# untitled.net
KiCad netlist of a schematic drawn in EAGLE
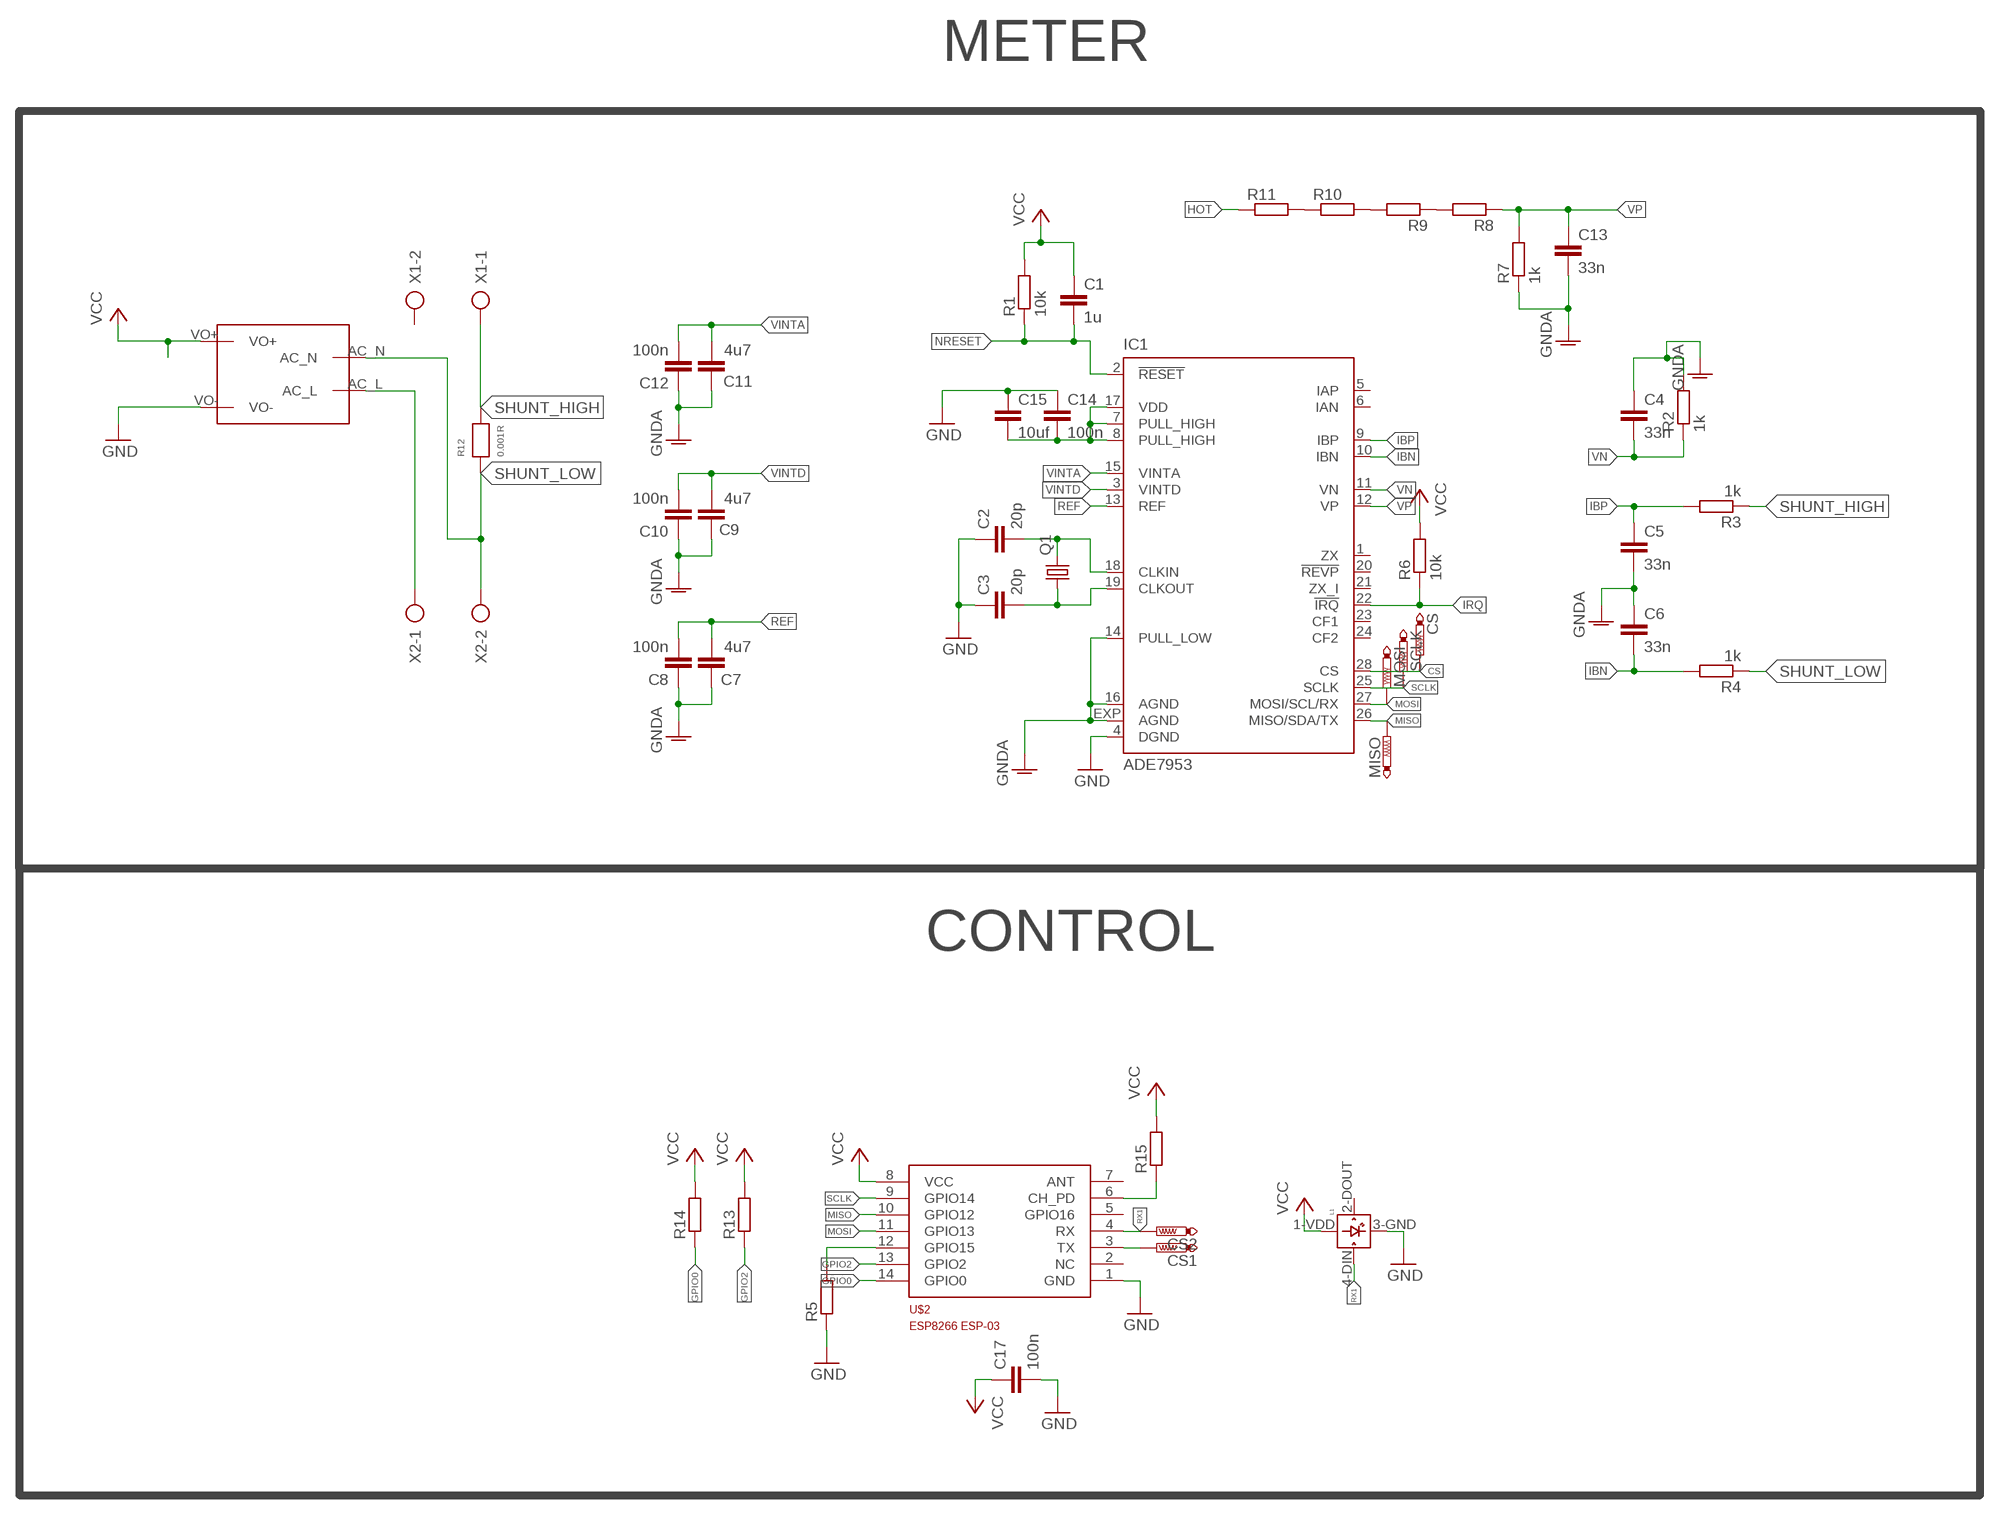
[diagram p0: schematic, sheet 1]

(export (version "E")
  (design (tool "Eeschema 10.0.6"))
  (components
    (comp (ref "C1")
      (value "1u")
      (footprint "eagle-import:C0805")
      (libsource (lib "eagle-import") (part "C-EUC0805"))
    )
    (comp (ref "C2")
      (value "20p")
      (footprint "eagle-import:C0805")
      (libsource (lib "eagle-import") (part "C-EUC0805"))
    )
    (comp (ref "C3")
      (value "20p")
      (footprint "eagle-import:C0805")
      (libsource (lib "eagle-import") (part "C-EUC0805"))
    )
    (comp (ref "C4")
      (value "33n")
      (footprint "eagle-import:C0805")
      (libsource (lib "eagle-import") (part "C-EUC0805"))
    )
    (comp (ref "C5")
      (value "33n")
      (footprint "eagle-import:C0805")
      (libsource (lib "eagle-import") (part "C-EUC0805"))
    )
    (comp (ref "C6")
      (value "33n")
      (footprint "eagle-import:C0805")
      (libsource (lib "eagle-import") (part "C-EUC0805"))
    )
    (comp (ref "C7")
      (value "4u7")
      (footprint "eagle-import:C0805")
      (libsource (lib "eagle-import") (part "C-EUC0805"))
    )
    (comp (ref "C8")
      (value "100n")
      (footprint "eagle-import:C0805")
      (libsource (lib "eagle-import") (part "C-EUC0805"))
    )
    (comp (ref "C9")
      (value "4u7")
      (footprint "eagle-import:C0805")
      (libsource (lib "eagle-import") (part "C-EUC0805"))
    )
    (comp (ref "C10")
      (value "100n")
      (footprint "eagle-import:C0805")
      (libsource (lib "eagle-import") (part "C-EUC0805"))
    )
    (comp (ref "C11")
      (value "4u7")
      (footprint "eagle-import:C0805")
      (libsource (lib "eagle-import") (part "C-EUC0805"))
    )
    (comp (ref "C12")
      (value "100n")
      (footprint "eagle-import:C0805")
      (libsource (lib "eagle-import") (part "C-EUC0805"))
    )
    (comp (ref "C13")
      (value "33n")
      (footprint "eagle-import:C0805")
      (libsource (lib "eagle-import") (part "C-EUC0805"))
    )
    (comp (ref "C14")
      (value "100n")
      (footprint "eagle-import:C0805")
      (libsource (lib "eagle-import") (part "C-EUC0805"))
    )
    (comp (ref "C15")
      (value "10uf")
      (footprint "eagle-import:C0805")
      (libsource (lib "eagle-import") (part "C-EUC0805"))
    )
    (comp (ref "C17")
      (value "100n")
      (footprint "eagle-import:C0805")
      (libsource (lib "eagle-import") (part "C-EUC0805"))
    )
    (comp (ref "CS")
      (value "PTR1B1,27")
      (footprint "eagle-import:B1,27")
      (libsource (lib "eagle-import") (part "PTR1B1,27"))
    )
    (comp (ref "CS1")
      (value "PTR1B1,27")
      (footprint "eagle-import:B1,27")
      (libsource (lib "eagle-import") (part "PTR1B1,27"))
    )
    (comp (ref "CS2")
      (value "PTR1B1,27")
      (footprint "eagle-import:B1,27")
      (libsource (lib "eagle-import") (part "PTR1B1,27"))
    )
    (comp (ref "IC1")
      (value "ADE7953")
      (footprint "eagle-import:QFN28-ML")
      (libsource (lib "eagle-import") (part "ADE7953"))
    )
    (comp (ref "L1")
      (value "WS2812B")
      (footprint "eagle-import:WS2812B")
      (libsource (lib "eagle-import") (part "WS2812B"))
    )
    (comp (ref "MISO")
      (value "PTR1B1,27")
      (footprint "eagle-import:B1,27")
      (libsource (lib "eagle-import") (part "PTR1B1,27"))
    )
    (comp (ref "MOSI")
      (value "PTR1B1,27")
      (footprint "eagle-import:B1,27")
      (libsource (lib "eagle-import") (part "PTR1B1,27"))
    )
    (comp (ref "Q1")
      (value "CRYSTALHC49UP")
      (footprint "eagle-import:HC49UP")
      (libsource (lib "eagle-import") (part "CRYSTALHC49UP"))
    )
    (comp (ref "R1")
      (value "10k")
      (footprint "eagle-import:R0805")
      (libsource (lib "eagle-import") (part "R-EU_R0805"))
    )
    (comp (ref "R2")
      (value "1k")
      (footprint "eagle-import:R0805")
      (libsource (lib "eagle-import") (part "R-EU_R0805"))
    )
    (comp (ref "R3")
      (value "1k")
      (footprint "eagle-import:R0805")
      (libsource (lib "eagle-import") (part "R-EU_R0805"))
    )
    (comp (ref "R4")
      (value "1k")
      (footprint "eagle-import:R0805")
      (libsource (lib "eagle-import") (part "R-EU_R0805"))
    )
    (comp (ref "R5")
      (value "R-EU_R0603")
      (footprint "eagle-import:R0603")
      (libsource (lib "eagle-import") (part "R-EU_R0603"))
    )
    (comp (ref "R6")
      (value "10k")
      (footprint "eagle-import:R0805")
      (libsource (lib "eagle-import") (part "R-EU_R0805"))
    )
    (comp (ref "R7")
      (value "1k")
      (footprint "eagle-import:R0805")
      (libsource (lib "eagle-import") (part "R-EU_R0805"))
    )
    (comp (ref "R8")
      (value "R-EU_R0805")
      (footprint "eagle-import:R0805")
      (libsource (lib "eagle-import") (part "R-EU_R0805"))
    )
    (comp (ref "R9")
      (value "R-EU_R0805")
      (footprint "eagle-import:R0805")
      (libsource (lib "eagle-import") (part "R-EU_R0805"))
    )
    (comp (ref "R10")
      (value "R-EU_R1206")
      (footprint "eagle-import:R1206")
      (libsource (lib "eagle-import") (part "R-EU_R1206"))
    )
    (comp (ref "R11")
      (value "R-EU_R1206")
      (footprint "eagle-import:R1206")
      (libsource (lib "eagle-import") (part "R-EU_R1206"))
    )
    (comp (ref "R12")
      (value "0.001R")
      (footprint "eagle-import:WRS-2_4527")
      (libsource (lib "eagle-import") (part "WSR-2_SHUNT"))
    )
    (comp (ref "R13")
      (value "R-EU_R0603")
      (footprint "eagle-import:R0603")
      (libsource (lib "eagle-import") (part "R-EU_R0603"))
    )
    (comp (ref "R14")
      (value "R-EU_R0603")
      (footprint "eagle-import:R0603")
      (libsource (lib "eagle-import") (part "R-EU_R0603"))
    )
    (comp (ref "R15")
      (value "R-EU_R0603")
      (footprint "eagle-import:R0603")
      (libsource (lib "eagle-import") (part "R-EU_R0603"))
    )
    (comp (ref "SCLK")
      (value "PTR1B1,27")
      (footprint "eagle-import:B1,27")
      (libsource (lib "eagle-import") (part "PTR1B1,27"))
    )
    (comp (ref "U$1")
      (value "MAINS_CONVERTERS")
      (footprint "eagle-import:HLK-PM01")
      (libsource (lib "eagle-import") (part "MAINS_CONVERTERS"))
    )
    (comp (ref "U$2")
      (value "ESP8266_ESP-03")
      (footprint "eagle-import:ESP-03")
      (libsource (lib "eagle-import") (part "ESP8266_ESP-03"))
    )
    (comp (ref "X1")
      (value "AK300/2")
      (footprint "eagle-import:AK300_2")
      (libsource (lib "eagle-import") (part "AK300/2"))
    )
    (comp (ref "X2")
      (value "AK300/2")
      (footprint "eagle-import:AK300_2")
      (libsource (lib "eagle-import") (part "AK300/2"))
    )
  )
  (nets
    (net (code "1") (name "CS") (class "Default")
      (node (ref "CS") (pin "TP") (pinfunction "TP_TP") (pintype "input"))
      (node (ref "IC1") (pin "28") (pinfunction "CS_28") (pintype "input"))
      (node (ref "R5") (pin "2") (pinfunction "2_2") (pintype "passive"))
      (node (ref "U$2") (pin "12") (pinfunction "GPIO15_12") (pintype "bidirectional"))
    )
    (net (code "2") (name "GND") (class "Default")
      (node (ref "C14") (pin "1") (pinfunction "1_1") (pintype "passive"))
      (node (ref "C15") (pin "1") (pinfunction "1_1") (pintype "passive"))
      (node (ref "C17") (pin "2") (pinfunction "2_2") (pintype "passive"))
      (node (ref "C2") (pin "1") (pinfunction "1_1") (pintype "passive"))
      (node (ref "C3") (pin "1") (pinfunction "1_1") (pintype "passive"))
      (node (ref "IC1") (pin "4") (pinfunction "DGND_4") (pintype "power_in"))
      (node (ref "L1") (pin "3-GND") (pinfunction "GND_3-GND") (pintype "bidirectional"))
      (node (ref "R5") (pin "1") (pinfunction "1_1") (pintype "passive"))
      (node (ref "U$1") (pin "VO-") (pinfunction "VO-_VO-") (pintype "output"))
      (node (ref "U$2") (pin "1") (pinfunction "GND_1") (pintype "bidirectional"))
    )
    (net (code "3") (name "GNDA") (class "Default")
      (node (ref "C10") (pin "1") (pinfunction "1_1") (pintype "passive"))
      (node (ref "C11") (pin "1") (pinfunction "1_1") (pintype "passive"))
      (node (ref "C12") (pin "1") (pinfunction "1_1") (pintype "passive"))
      (node (ref "C13") (pin "2") (pinfunction "2_2") (pintype "passive"))
      (node (ref "C4") (pin "1") (pinfunction "1_1") (pintype "passive"))
      (node (ref "C5") (pin "2") (pinfunction "2_2") (pintype "passive"))
      (node (ref "C6") (pin "1") (pinfunction "1_1") (pintype "passive"))
      (node (ref "C7") (pin "1") (pinfunction "1_1") (pintype "passive"))
      (node (ref "C8") (pin "1") (pinfunction "1_1") (pintype "passive"))
      (node (ref "C9") (pin "1") (pinfunction "1_1") (pintype "passive"))
      (node (ref "IC1") (pin "14") (pinfunction "PULL_LOW_14") (pintype "input"))
      (node (ref "IC1") (pin "16") (pinfunction "AGND_16") (pintype "power_in"))
      (node (ref "IC1") (pin "EXP") (pinfunction "AGND_EXP") (pintype "power_in"))
      (node (ref "R2") (pin "2") (pinfunction "2_2") (pintype "passive"))
      (node (ref "R7") (pin "1") (pinfunction "1_1") (pintype "passive"))
    )
    (net (code "4") (name "GPIO0") (class "Default")
      (node (ref "R14") (pin "1") (pinfunction "1_1") (pintype "passive"))
      (node (ref "U$2") (pin "14") (pinfunction "GPIO0_14") (pintype "bidirectional"))
    )
    (net (code "5") (name "GPIO2") (class "Default")
      (node (ref "R13") (pin "1") (pinfunction "1_1") (pintype "passive"))
      (node (ref "U$2") (pin "13") (pinfunction "GPIO2_13") (pintype "bidirectional"))
    )
    (net (code "6") (name "HOT") (class "Default")
      (node (ref "R11") (pin "1") (pinfunction "1_1") (pintype "passive"))
      (node (ref "U$1") (pin "AC_L") (pinfunction "AC_L_AC_L") (pintype "input"))
      (node (ref "X2") (pin "1") (pinfunction "KL_1") (pintype "passive"))
    )
    (net (code "7") (name "IBN") (class "Default")
      (node (ref "C6") (pin "2") (pinfunction "2_2") (pintype "passive"))
      (node (ref "IC1") (pin "10") (pinfunction "IBN_10") (pintype "input"))
      (node (ref "R4") (pin "2") (pinfunction "2_2") (pintype "passive"))
    )
    (net (code "8") (name "IBP") (class "Default")
      (node (ref "C5") (pin "1") (pinfunction "1_1") (pintype "passive"))
      (node (ref "IC1") (pin "9") (pinfunction "IBP_9") (pintype "input"))
      (node (ref "R3") (pin "2") (pinfunction "2_2") (pintype "passive"))
    )
    (net (code "9") (name "IRQ") (class "Default")
      (node (ref "IC1") (pin "22") (pinfunction "~{IRQ}_22") (pintype "output"))
      (node (ref "R6") (pin "1") (pinfunction "1_1") (pintype "passive"))
    )
    (net (code "10") (name "MISO") (class "Default")
      (node (ref "IC1") (pin "26") (pinfunction "MISO/SDA/TX_26") (pintype "output"))
      (node (ref "MISO") (pin "TP") (pinfunction "TP_TP") (pintype "input"))
      (node (ref "U$2") (pin "10") (pinfunction "GPIO12_10") (pintype "bidirectional"))
    )
    (net (code "11") (name "MOSI") (class "Default")
      (node (ref "IC1") (pin "27") (pinfunction "MOSI/SCL/RX_27") (pintype "input"))
      (node (ref "MOSI") (pin "TP") (pinfunction "TP_TP") (pintype "input"))
      (node (ref "U$2") (pin "11") (pinfunction "GPIO13_11") (pintype "bidirectional"))
    )
    (net (code "12") (name "NRESET") (class "Default")
      (node (ref "C1") (pin "2") (pinfunction "2_2") (pintype "passive"))
      (node (ref "IC1") (pin "2") (pinfunction "~{RESET}_2") (pintype "input"))
      (node (ref "R1") (pin "1") (pinfunction "1_1") (pintype "passive"))
    )
    (net (code "13") (name "Net-(IC1-CLKIN)") (class "Default")
      (node (ref "C2") (pin "2") (pinfunction "2_2") (pintype "passive"))
      (node (ref "IC1") (pin "18") (pinfunction "CLKIN_18") (pintype "input"))
      (node (ref "Q1") (pin "2") (pinfunction "2_2") (pintype "passive"))
    )
    (net (code "14") (name "Net-(IC1-CLKOUT)") (class "Default")
      (node (ref "C3") (pin "2") (pinfunction "2_2") (pintype "passive"))
      (node (ref "IC1") (pin "19") (pinfunction "CLKOUT_19") (pintype "output"))
      (node (ref "Q1") (pin "1") (pinfunction "1_1") (pintype "passive"))
    )
    (net (code "15") (name "Net-(R8-Pad2)") (class "Default")
      (node (ref "R8") (pin "2") (pinfunction "2_2") (pintype "passive"))
      (node (ref "R9") (pin "1") (pinfunction "1_1") (pintype "passive"))
    )
    (net (code "16") (name "Net-(R10-Pad1)") (class "Default")
      (node (ref "R10") (pin "1") (pinfunction "1_1") (pintype "passive"))
      (node (ref "R11") (pin "2") (pinfunction "2_2") (pintype "passive"))
    )
    (net (code "17") (name "Net-(R10-Pad2)") (class "Default")
      (node (ref "R10") (pin "2") (pinfunction "2_2") (pintype "passive"))
      (node (ref "R9") (pin "2") (pinfunction "2_2") (pintype "passive"))
    )
    (net (code "18") (name "Net-(U$2-CH_PD)") (class "Default")
      (node (ref "R15") (pin "1") (pinfunction "1_1") (pintype "passive"))
      (node (ref "U$2") (pin "6") (pinfunction "CH_PD_6") (pintype "bidirectional"))
    )
    (net (code "19") (name "Net-(U$2-TX)") (class "Default")
      (node (ref "CS1") (pin "TP") (pinfunction "TP_TP") (pintype "input"))
      (node (ref "U$2") (pin "3") (pinfunction "TX_3") (pintype "bidirectional"))
    )
    (net (code "20") (name "REF") (class "Default")
      (node (ref "C7") (pin "2") (pinfunction "2_2") (pintype "passive"))
      (node (ref "C8") (pin "2") (pinfunction "2_2") (pintype "passive"))
      (node (ref "IC1") (pin "13") (pinfunction "REF_13") (pintype "output"))
    )
    (net (code "21") (name "RX1") (class "Default")
      (node (ref "CS2") (pin "TP") (pinfunction "TP_TP") (pintype "input"))
      (node (ref "L1") (pin "4-DIN") (pinfunction "DIN_4-DIN") (pintype "input"))
      (node (ref "U$2") (pin "4") (pinfunction "RX_4") (pintype "bidirectional"))
    )
    (net (code "22") (name "SCLK") (class "Default")
      (node (ref "IC1") (pin "25") (pinfunction "SCLK_25") (pintype "input"))
      (node (ref "SCLK") (pin "TP") (pinfunction "TP_TP") (pintype "input"))
      (node (ref "U$2") (pin "9") (pinfunction "GPIO14_9") (pintype "bidirectional"))
    )
    (net (code "23") (name "SHUNT_HIGH") (class "Default")
      (node (ref "R12") (pin "2") (pinfunction "2_2") (pintype "bidirectional"))
      (node (ref "R3") (pin "1") (pinfunction "1_1") (pintype "passive"))
      (node (ref "X1") (pin "1") (pinfunction "KL_1") (pintype "passive"))
    )
    (net (code "24") (name "SHUNT_LOW") (class "Default")
      (node (ref "R12") (pin "1") (pinfunction "1_1") (pintype "bidirectional"))
      (node (ref "R4") (pin "1") (pinfunction "1_1") (pintype "passive"))
      (node (ref "U$1") (pin "AC_N") (pinfunction "AC_N_AC_N") (pintype "input"))
      (node (ref "X2") (pin "2") (pinfunction "KL_2") (pintype "passive"))
    )
    (net (code "25") (name "VCC") (class "Default")
      (node (ref "C1") (pin "1") (pinfunction "1_1") (pintype "passive"))
      (node (ref "C14") (pin "2") (pinfunction "2_2") (pintype "passive"))
      (node (ref "C15") (pin "2") (pinfunction "2_2") (pintype "passive"))
      (node (ref "C17") (pin "1") (pinfunction "1_1") (pintype "passive"))
      (node (ref "IC1") (pin "17") (pinfunction "VDD_17") (pintype "power_in"))
      (node (ref "IC1") (pin "7") (pinfunction "PULL_HIGH_7") (pintype "input"))
      (node (ref "IC1") (pin "8") (pinfunction "PULL_HIGH_8") (pintype "input"))
      (node (ref "L1") (pin "1-VDD") (pinfunction "VDD_1-VDD") (pintype "bidirectional"))
      (node (ref "R1") (pin "2") (pinfunction "2_2") (pintype "passive"))
      (node (ref "R13") (pin "2") (pinfunction "2_2") (pintype "passive"))
      (node (ref "R14") (pin "2") (pinfunction "2_2") (pintype "passive"))
      (node (ref "R15") (pin "2") (pinfunction "2_2") (pintype "passive"))
      (node (ref "R6") (pin "2") (pinfunction "2_2") (pintype "passive"))
      (node (ref "U$1") (pin "VO+") (pinfunction "VO+_VO+") (pintype "output"))
      (node (ref "U$2") (pin "8") (pinfunction "VCC_8") (pintype "bidirectional"))
    )
    (net (code "26") (name "VINTA") (class "Default")
      (node (ref "C11") (pin "2") (pinfunction "2_2") (pintype "passive"))
      (node (ref "C12") (pin "2") (pinfunction "2_2") (pintype "passive"))
      (node (ref "IC1") (pin "15") (pinfunction "VINTA_15") (pintype "output"))
    )
    (net (code "27") (name "VINTD") (class "Default")
      (node (ref "C10") (pin "2") (pinfunction "2_2") (pintype "passive"))
      (node (ref "C9") (pin "2") (pinfunction "2_2") (pintype "passive"))
      (node (ref "IC1") (pin "3") (pinfunction "VINTD_3") (pintype "output"))
    )
    (net (code "28") (name "VN") (class "Default")
      (node (ref "C4") (pin "2") (pinfunction "2_2") (pintype "passive"))
      (node (ref "IC1") (pin "11") (pinfunction "VN_11") (pintype "input"))
      (node (ref "R2") (pin "1") (pinfunction "1_1") (pintype "passive"))
    )
    (net (code "29") (name "VP") (class "Default")
      (node (ref "C13") (pin "1") (pinfunction "1_1") (pintype "passive"))
      (node (ref "IC1") (pin "12") (pinfunction "VP_12") (pintype "input"))
      (node (ref "R7") (pin "2") (pinfunction "2_2") (pintype "passive"))
      (node (ref "R8") (pin "1") (pinfunction "1_1") (pintype "passive"))
    )
    (net (code "30") (name "unconnected-(IC1-CF1-Pad23)") (class "Default")
      (node (ref "IC1") (pin "23") (pinfunction "CF1_23") (pintype "output"))
    )
    (net (code "31") (name "unconnected-(IC1-CF2-Pad24)") (class "Default")
      (node (ref "IC1") (pin "24") (pinfunction "CF2_24") (pintype "output"))
    )
    (net (code "32") (name "unconnected-(IC1-IAN-Pad6)") (class "Default")
      (node (ref "IC1") (pin "6") (pinfunction "IAN_6") (pintype "input"))
    )
    (net (code "33") (name "unconnected-(IC1-IAP-Pad5)") (class "Default")
      (node (ref "IC1") (pin "5") (pinfunction "IAP_5") (pintype "input"))
    )
    (net (code "34") (name "unconnected-(IC1-ZX-Pad1)") (class "Default")
      (node (ref "IC1") (pin "1") (pinfunction "ZX_1") (pintype "output"))
    )
    (net (code "35") (name "unconnected-(IC1-ZX_I-Pad21)") (class "Default")
      (node (ref "IC1") (pin "21") (pinfunction "ZX_I_21") (pintype "output"))
    )
    (net (code "36") (name "unconnected-(IC1-~{REVP}-Pad20)") (class "Default")
      (node (ref "IC1") (pin "20") (pinfunction "~{REVP}_20") (pintype "output"))
    )
    (net (code "37") (name "unconnected-(L1-DOUT-Pad2-DOUT)") (class "Default")
      (node (ref "L1") (pin "2-DOUT") (pinfunction "DOUT_2-DOUT") (pintype "output"))
    )
    (net (code "38") (name "unconnected-(U$2-ANT-Pad7)") (class "Default")
      (node (ref "U$2") (pin "7") (pinfunction "ANT_7") (pintype "bidirectional"))
    )
    (net (code "39") (name "unconnected-(U$2-GPIO16-Pad5)") (class "Default")
      (node (ref "U$2") (pin "5") (pinfunction "GPIO16_5") (pintype "bidirectional"))
    )
    (net (code "40") (name "unconnected-(U$2-NC-Pad2)") (class "Default")
      (node (ref "U$2") (pin "2") (pinfunction "NC_2") (pintype "bidirectional"))
    )
    (net (code "41") (name "unconnected-(X1B-KL-Pad2)") (class "Default")
      (node (ref "X1") (pin "2") (pinfunction "KL_2") (pintype "passive"))
    )
  )
)
